# offworld1.net
KiCad netlist of a schematic drawn in EAGLE
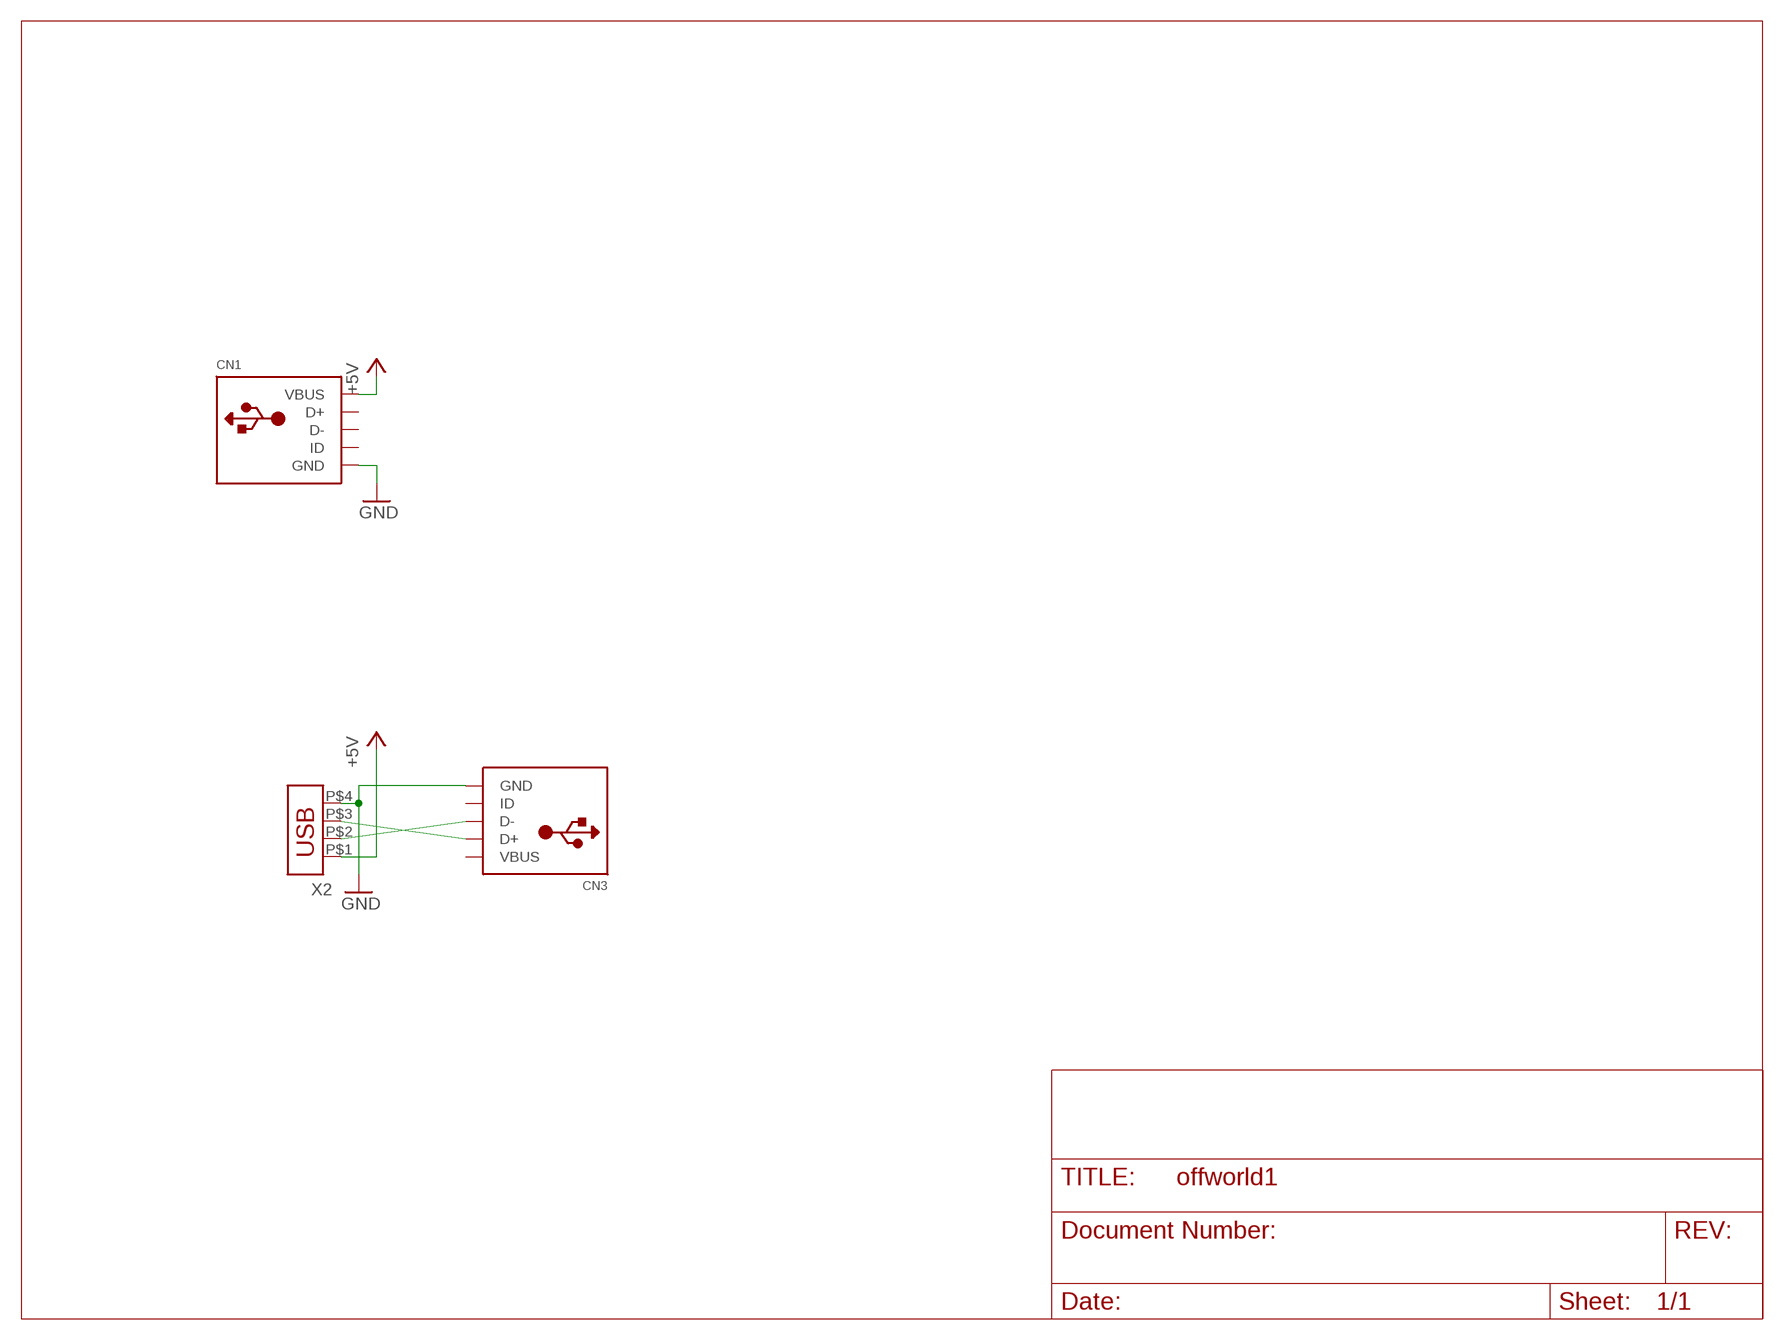
[diagram p0: schematic, sheet 1]

(export (version "E")
  (design (tool "Eeschema 10.0.6"))
  (components
    (comp (ref "CN1")
      (value "USBMOLEX")
      (footprint "eagle-import:USB-MINIB-THM-MOLEX")
      (libsource (lib "eagle-import") (part "USBMOLEX"))
    )
    (comp (ref "CN3")
      (value "USBMOLEX")
      (footprint "eagle-import:USB-MINIB-THM-MOLEX")
      (libsource (lib "eagle-import") (part "USBMOLEX"))
    )
    (comp (ref "X2")
      (value "USB-787616MID")
      (footprint "eagle-import:USBA-MID")
      (libsource (lib "eagle-import") (part "USB-787616MID"))
    )
  )
  (nets
    (net (code "1") (name "+5V") (class "Default")
      (node (ref "CN1") (pin "VBUS") (pinfunction "VBUS_VBUS") (pintype "power_in"))
      (node (ref "X2") (pin "P$1") (pinfunction "1_P$1") (pintype "passive"))
    )
    (net (code "2") (name "/VBUS") (class "Default")
      (node (ref "CN3") (pin "VBUS") (pinfunction "VBUS_VBUS") (pintype "power_in"))
    )
    (net (code "3") (name "GND") (class "Default")
      (node (ref "CN1") (pin "GND") (pinfunction "GND_GND") (pintype "power_in"))
      (node (ref "CN3") (pin "GND") (pinfunction "GND_GND") (pintype "power_in"))
      (node (ref "X2") (pin "P$4") (pinfunction "4_P$4") (pintype "passive"))
    )
    (net (code "4") (name "Net-(X2-2)") (class "Default")
      (node (ref "CN3") (pin "D-") (pinfunction "D-_D-") (pintype "bidirectional"))
      (node (ref "X2") (pin "P$2") (pinfunction "2_P$2") (pintype "passive"))
    )
    (net (code "5") (name "Net-(X2-3)") (class "Default")
      (node (ref "CN3") (pin "D+") (pinfunction "D+_D+") (pintype "bidirectional"))
      (node (ref "X2") (pin "P$3") (pinfunction "3_P$3") (pintype "passive"))
    )
    (net (code "6") (name "unconnected-(CN1-PadD+)") (class "Default")
      (node (ref "CN1") (pin "D+") (pinfunction "D+_D+") (pintype "bidirectional"))
    )
    (net (code "7") (name "unconnected-(CN1-PadD-)") (class "Default")
      (node (ref "CN1") (pin "D-") (pinfunction "D-_D-") (pintype "bidirectional"))
    )
    (net (code "8") (name "unconnected-(CN1-PadID)") (class "Default")
      (node (ref "CN1") (pin "ID") (pinfunction "ID_ID") (pintype "bidirectional"))
    )
    (net (code "9") (name "unconnected-(CN3-PadID)") (class "Default")
      (node (ref "CN3") (pin "ID") (pinfunction "ID_ID") (pintype "bidirectional"))
    )
  )
)
